# ProProject_HV_Display_2024-06-08.net
KiCad netlist of a schematic drawn in EasyEDA Pro
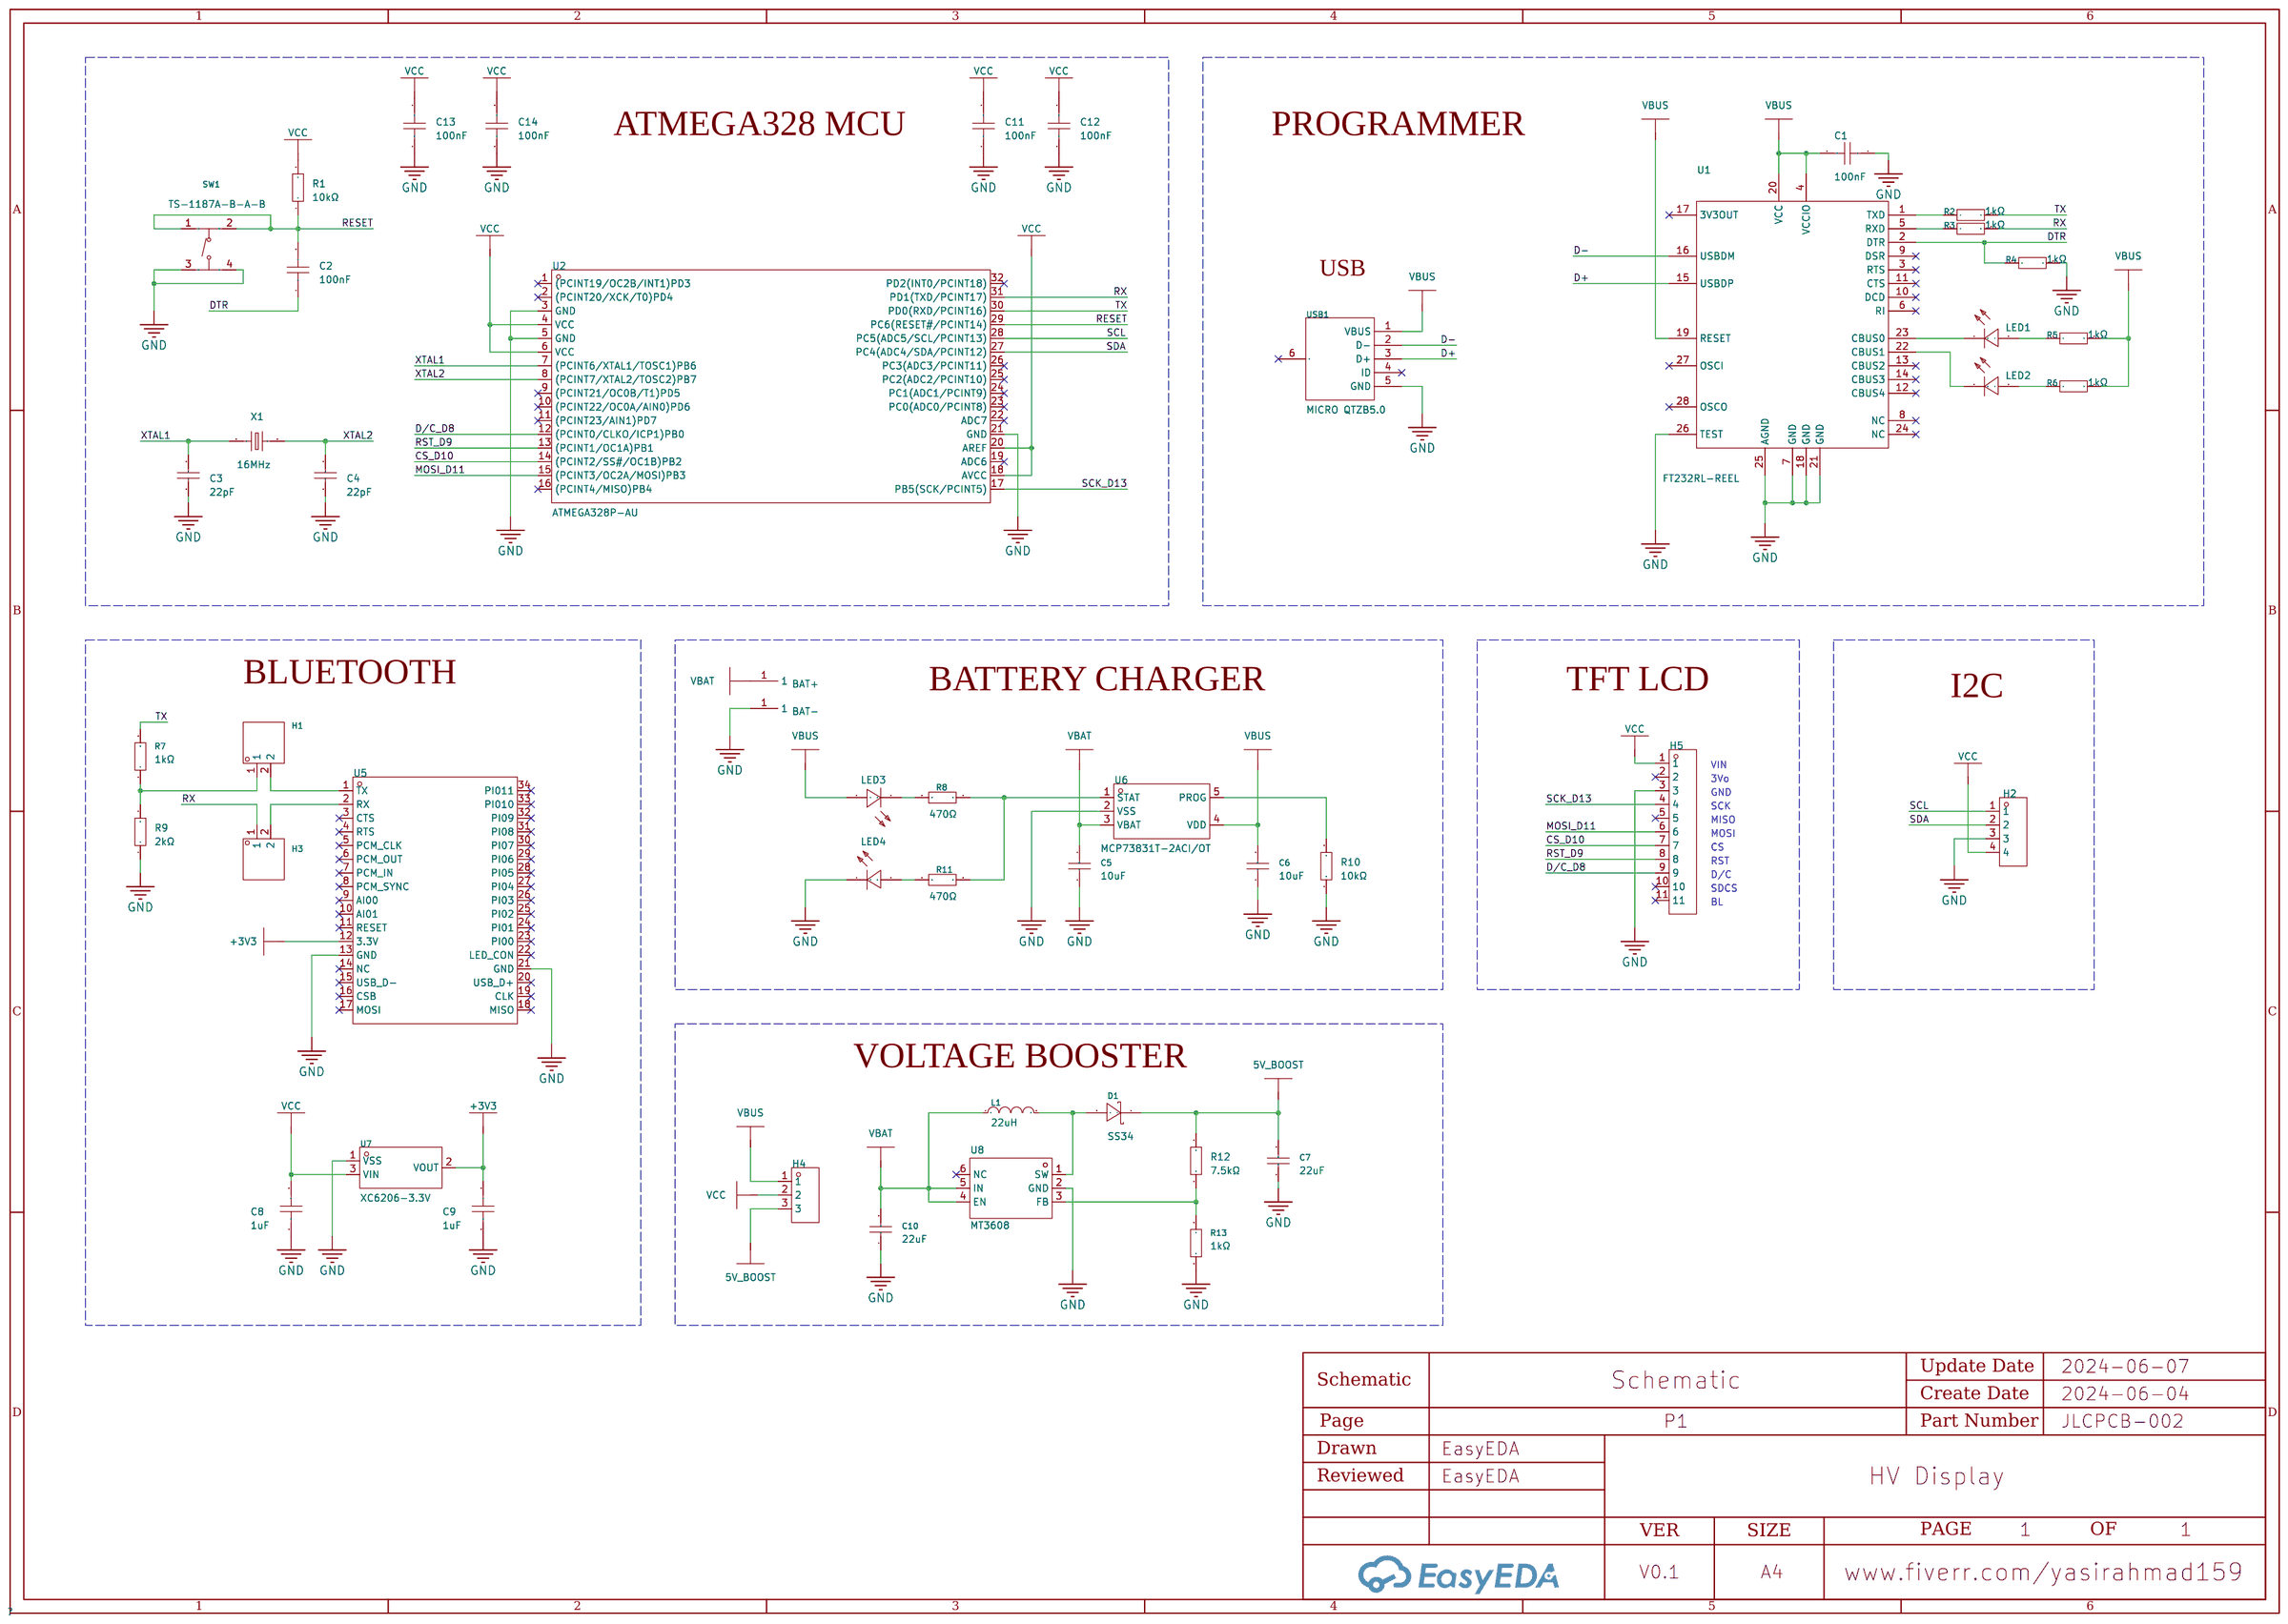
[diagram p0: schematic sheet]

(export (version "E")
  (design (tool "Eeschema 10.0.6"))
  (components
    (comp (ref "C1")
      (value "100nF")
      (footprint "easyedapro:C0402")
      (fields
        (field (name "Manufacturer Part") "CL05B104KB54PNC")
        (field (name "Manufacturer") "SAMSUNG(三星)")
      )
      (libsource (lib "easyedapro") (part "CL05B104KB54PNC"))
    )
    (comp (ref "C2")
      (value "100nF")
      (footprint "easyedapro:C0402")
      (fields
        (field (name "Manufacturer Part") "CL05B104KB54PNC")
        (field (name "Manufacturer") "SAMSUNG(三星)")
      )
      (libsource (lib "easyedapro") (part "CL05B104KB54PNC"))
    )
    (comp (ref "C3")
      (value "22pF")
      (footprint "easyedapro:C0402")
      (fields (field (name "Manufacturer Part") "0402CG220J500NT") (field (name "Manufacturer") "FH(风华)"))
      (libsource (lib "easyedapro") (part "0402CG220J500NT"))
    )
    (comp (ref "C4")
      (value "22pF")
      (footprint "easyedapro:C0402")
      (fields (field (name "Manufacturer Part") "0402CG220J500NT") (field (name "Manufacturer") "FH(风华)"))
      (libsource (lib "easyedapro") (part "0402CG220J500NT"))
    )
    (comp (ref "C5")
      (value "10uF")
      (footprint "easyedapro:C0402")
      (fields
        (field (name "Manufacturer Part") "CL05A106MQ5NUNC")
        (field (name "Manufacturer") "SAMSUNG(三星)")
      )
      (libsource (lib "easyedapro") (part "CL05A106MQ5NUNC"))
    )
    (comp (ref "C6")
      (value "10uF")
      (footprint "easyedapro:C0402")
      (fields
        (field (name "Manufacturer Part") "CL05A106MQ5NUNC")
        (field (name "Manufacturer") "SAMSUNG(三星)")
      )
      (libsource (lib "easyedapro") (part "CL05A106MQ5NUNC"))
    )
    (comp (ref "C7")
      (value "22uF")
      (footprint "easyedapro:C1812")
      (fields (field (name "Manufacturer Part") "1812X226K250NT") (field (name "Manufacturer") "FH(风华)"))
      (libsource (lib "easyedapro") (part "1812X226K250NT"))
    )
    (comp (ref "C8")
      (value "1uF")
      (footprint "easyedapro:C0402")
      (fields
        (field (name "Manufacturer Part") "CL05A105KA5NQNC")
        (field (name "Manufacturer") "SAMSUNG(三星)")
      )
      (libsource (lib "easyedapro") (part "CL05A105KA5NQNC"))
    )
    (comp (ref "C9")
      (value "1uF")
      (footprint "easyedapro:C0402")
      (fields
        (field (name "Manufacturer Part") "CL05A105KA5NQNC")
        (field (name "Manufacturer") "SAMSUNG(三星)")
      )
      (libsource (lib "easyedapro") (part "CL05A105KA5NQNC"))
    )
    (comp (ref "C10")
      (value "22uF")
      (footprint "easyedapro:C1812")
      (fields (field (name "Manufacturer Part") "1812X226K250NT") (field (name "Manufacturer") "FH(风华)"))
      (libsource (lib "easyedapro") (part "1812X226K250NT"))
    )
    (comp (ref "C11")
      (value "100nF")
      (footprint "easyedapro:C0402")
      (fields
        (field (name "Manufacturer Part") "CL05B104KB54PNC")
        (field (name "Manufacturer") "SAMSUNG(三星)")
      )
      (libsource (lib "easyedapro") (part "CL05B104KB54PNC"))
    )
    (comp (ref "C12")
      (value "100nF")
      (footprint "easyedapro:C0402")
      (fields
        (field (name "Manufacturer Part") "CL05B104KB54PNC")
        (field (name "Manufacturer") "SAMSUNG(三星)")
      )
      (libsource (lib "easyedapro") (part "CL05B104KB54PNC"))
    )
    (comp (ref "C13")
      (value "100nF")
      (footprint "easyedapro:C0402")
      (fields
        (field (name "Manufacturer Part") "CL05B104KB54PNC")
        (field (name "Manufacturer") "SAMSUNG(三星)")
      )
      (libsource (lib "easyedapro") (part "CL05B104KB54PNC"))
    )
    (comp (ref "C14")
      (value "100nF")
      (footprint "easyedapro:C0402")
      (fields
        (field (name "Manufacturer Part") "CL05B104KB54PNC")
        (field (name "Manufacturer") "SAMSUNG(三星)")
      )
      (libsource (lib "easyedapro") (part "CL05B104KB54PNC"))
    )
    (comp (ref "D1")
      (value "SS34")
      (footprint "easyedapro:SMA_L4.3-W2.6-LS5.2-RD")
      (fields (field (name "Manufacturer") "MDD"))
      (libsource (lib "easyedapro") (part "SS34_C8678"))
    )
    (comp (ref "H1")
      (value "~")
      (footprint "easyedapro:HDR-TH_2P-P2.54-V-M-1")
      (libsource (lib "easyedapro") (part "210S-1*2P L=11.6MMGold-plated black"))
    )
    (comp (ref "H2")
      (value "~")
      (footprint "easyedapro:HDR-TH_4P-P2.54-V-M")
      (libsource (lib "easyedapro") (part "PZ254V-11-04P"))
    )
    (comp (ref "H3")
      (value "~")
      (footprint "easyedapro:HDR-TH_2P-P2.54-V-M-1")
      (libsource (lib "easyedapro") (part "210S-1*2P L=11.6MMGold-plated black"))
    )
    (comp (ref "H4")
      (value "~")
      (footprint "easyedapro:HDR-TH_3P-P2.54-V-M")
      (libsource (lib "easyedapro") (part "PZ254V-11-03P_C2937625"))
    )
    (comp (ref "H5")
      (value "~")
      (footprint "easyedapro:HDR-TH_11P-P2.54-V-M")
      (libsource (lib "easyedapro") (part "PZ254-1-11-Z-8.5"))
    )
    (comp (ref "L1")
      (value "22uH")
      (footprint "easyedapro:IND-SMD_L7.0-W6.8")
      (fields (field (name "Manufacturer Part") "SMRH74-220MT") (field (name "Manufacturer") "SXN(顺翔诺)"))
      (libsource (lib "easyedapro") (part "SMRH74-220MT"))
    )
    (comp (ref "LED1")
      (value "TJ-S1005SW4TGLC2R-A5")
      (footprint "easyedapro:LED0402-RD")
      (description "Emitted Color:Red")
      (fields (field (name "Manufacturer") "TOGIALED(统佳)"))
      (libsource (lib "easyedapro") (part "TJ-S1005SW4TGLC2R-A5"))
    )
    (comp (ref "LED2")
      (value "TJ-S1005SW4TGLC2R-A5")
      (footprint "easyedapro:LED0402-RD")
      (description "Emitted Color:Red")
      (fields (field (name "Manufacturer") "TOGIALED(统佳)"))
      (libsource (lib "easyedapro") (part "TJ-S1005SW4TGLC2R-A5"))
    )
    (comp (ref "LED3")
      (value "TJ-S1005SW4TGLC2R-A5")
      (footprint "easyedapro:LED0402-RD")
      (description "Emitted Color:Red")
      (fields (field (name "Manufacturer") "TOGIALED(统佳)"))
      (libsource (lib "easyedapro") (part "TJ-S1005SW4TGLC2R-A5"))
    )
    (comp (ref "LED4")
      (value "TJ-S1005SW4TGLC7K-A5")
      (footprint "easyedapro:LED0402-RD_GREEN")
      (description "Emitted Color:Green-yellow")
      (fields (field (name "Manufacturer") "TOGIALED(统佳)"))
      (libsource (lib "easyedapro") (part "TJ-S1005SW4TGLC7K-A5"))
    )
    (comp (ref "R1")
      (value "10kΩ")
      (footprint "easyedapro:R0402")
      (fields
        (field (name "Manufacturer Part") "0402WGF1002TCE")
        (field (name "Manufacturer") "UNI-ROYAL(厚声)")
      )
      (libsource (lib "easyedapro") (part "0402WGF1002TCE"))
    )
    (comp (ref "R2")
      (value "1kΩ")
      (footprint "easyedapro:R0402")
      (fields
        (field (name "Manufacturer Part") "0402WGF1001TCE")
        (field (name "Manufacturer") "UNI-ROYAL(厚声)")
      )
      (libsource (lib "easyedapro") (part "0402WGF1001TCE"))
    )
    (comp (ref "R3")
      (value "1kΩ")
      (footprint "easyedapro:R0402")
      (fields
        (field (name "Manufacturer Part") "0402WGF1001TCE")
        (field (name "Manufacturer") "UNI-ROYAL(厚声)")
      )
      (libsource (lib "easyedapro") (part "0402WGF1001TCE"))
    )
    (comp (ref "R4")
      (value "1kΩ")
      (footprint "easyedapro:R0402")
      (fields
        (field (name "Manufacturer Part") "0402WGF1001TCE")
        (field (name "Manufacturer") "UNI-ROYAL(厚声)")
      )
      (libsource (lib "easyedapro") (part "0402WGF1001TCE"))
    )
    (comp (ref "R5")
      (value "1kΩ")
      (footprint "easyedapro:R0402")
      (fields
        (field (name "Manufacturer Part") "0402WGF1001TCE")
        (field (name "Manufacturer") "UNI-ROYAL(厚声)")
      )
      (libsource (lib "easyedapro") (part "0402WGF1001TCE"))
    )
    (comp (ref "R6")
      (value "1kΩ")
      (footprint "easyedapro:R0402")
      (fields
        (field (name "Manufacturer Part") "0402WGF1001TCE")
        (field (name "Manufacturer") "UNI-ROYAL(厚声)")
      )
      (libsource (lib "easyedapro") (part "0402WGF1001TCE"))
    )
    (comp (ref "R7")
      (value "1kΩ")
      (footprint "easyedapro:R0402")
      (fields
        (field (name "Manufacturer Part") "0402WGF1001TCE")
        (field (name "Manufacturer") "UNI-ROYAL(厚声)")
      )
      (libsource (lib "easyedapro") (part "0402WGF1001TCE"))
    )
    (comp (ref "R8")
      (value "470Ω")
      (footprint "easyedapro:R0402")
      (fields
        (field (name "Manufacturer Part") "0402WGF4700TCE")
        (field (name "Manufacturer") "UNI-ROYAL(厚声)")
      )
      (libsource (lib "easyedapro") (part "0402WGF4700TCE"))
    )
    (comp (ref "R9")
      (value "2kΩ")
      (footprint "easyedapro:R0402")
      (fields
        (field (name "Manufacturer Part") "0402WGF2001TCE")
        (field (name "Manufacturer") "UNI-ROYAL(厚声)")
      )
      (libsource (lib "easyedapro") (part "0402WGF2001TCE"))
    )
    (comp (ref "R10")
      (value "10kΩ")
      (footprint "easyedapro:R0402")
      (fields
        (field (name "Manufacturer Part") "0402WGF1002TCE")
        (field (name "Manufacturer") "UNI-ROYAL(厚声)")
      )
      (libsource (lib "easyedapro") (part "0402WGF1002TCE"))
    )
    (comp (ref "R11")
      (value "470Ω")
      (footprint "easyedapro:R0402")
      (fields
        (field (name "Manufacturer Part") "0402WGF4700TCE")
        (field (name "Manufacturer") "UNI-ROYAL(厚声)")
      )
      (libsource (lib "easyedapro") (part "0402WGF4700TCE"))
    )
    (comp (ref "R12")
      (value "7.5kΩ")
      (footprint "easyedapro:R0402")
      (fields (field (name "Manufacturer Part") "WR04X7501FTL") (field (name "Manufacturer") "Walsin(华新科)"))
      (libsource (lib "easyedapro") (part "WR04X7501FTL"))
    )
    (comp (ref "R13")
      (value "1kΩ")
      (footprint "easyedapro:R0402")
      (fields
        (field (name "Manufacturer Part") "0402WGF1001TCE")
        (field (name "Manufacturer") "UNI-ROYAL(厚声)")
      )
      (libsource (lib "easyedapro") (part "0402WGF1001TCE"))
    )
    (comp (ref "SW1")
      (value "TS-1187A-B-A-B")
      (footprint "easyedapro:SW-SMD_4P-L5.1-W5.1-P3.70-LS6.5-TL-2")
      (fields (field (name "Manufacturer") "XKB Connectivity(中国星坤)"))
      (libsource (lib "easyedapro") (part "TS-1187A-B-A-B"))
    )
    (comp (ref "U1")
      (value "FT232RL-REEL")
      (footprint "easyedapro:SSOP-28_L10.2-W5.3-P0.65-LS7.8-BL")
      (fields (field (name "Manufacturer") "FTDI(飞特帝亚)"))
      (libsource (lib "easyedapro") (part "FT232RL-REEL"))
    )
    (comp (ref "U2")
      (value "ATMEGA328P-AU")
      (footprint "easyedapro:TQFP-32_L7.0-W7.0-P0.80-LS9.0-BL")
      (fields (field (name "Manufacturer") "MICROCHIP(美国微芯)"))
      (libsource (lib "easyedapro") (part "ATMEGA328P-AU"))
    )
    (comp (ref "U3")
      (value "BAT+")
      (footprint "easyedapro:TESTPOINT-TH_BD3.2")
      (fields (field (name "Manufacturer Part") "TP-黑色测试点"))
      (libsource (lib "easyedapro") (part "TP-黑色测试点"))
    )
    (comp (ref "U4")
      (value "BAT-")
      (footprint "easyedapro:TESTPOINT-TH_BD3.2")
      (fields (field (name "Manufacturer Part") "TP-黑色测试点"))
      (libsource (lib "easyedapro") (part "TP-黑色测试点"))
    )
    (comp (ref "U5")
      (value "{ManufacturerPart!}")
      (footprint "easyedapro:BULETM-SMD_HC-05")
      (fields (field (name "Manufacturer Part") "HC-05"))
      (libsource (lib "easyedapro") (part "HC-05"))
    )
    (comp (ref "U6")
      (value "MCP73831T-2ACI/OT")
      (footprint "easyedapro:SOT-23-5_L3.0-W1.7-P0.95-LS2.8-BL")
      (fields (field (name "Manufacturer") "MICROCHIP(美国微芯)"))
      (libsource (lib "easyedapro") (part "MCP73831T-2ACI/OT"))
    )
    (comp (ref "U7")
      (value "XC6206-3.3V")
      (footprint "easyedapro:SSOT-3_L2.9-W1.6-P0.95-LS2.8-BR")
      (fields (field (name "Manufacturer") "YONGYUTAI(永裕泰)"))
      (libsource (lib "easyedapro") (part "XC6206-3.3V"))
    )
    (comp (ref "U8")
      (value "MT3608")
      (footprint "easyedapro:SOT-23-6_L2.9-W1.6-P0.95-LS2.8-BL")
      (fields (field (name "Manufacturer") "西安航天民芯"))
      (libsource (lib "easyedapro") (part "MT3608"))
    )
    (comp (ref "USB1")
      (value "MICRO QTZB5.0")
      (footprint "easyedapro:MICRO-USB-SMD_MICRO-QTZB5.0")
      (fields (field (name "Manufacturer") "SHOU HAN(首韩)"))
      (libsource (lib "easyedapro") (part "MICRO QTZB5.0"))
    )
    (comp (ref "X1")
      (value "16MHz")
      (footprint "easyedapro:HC-49S_L11.4-W4.8")
      (fields (field (name "Manufacturer Part") "TAXM16M2GLFBET2T") (field (name "Manufacturer") "YJX(雅晶鑫)"))
      (libsource (lib "easyedapro") (part "HC-49SM16MHz20pF30ppm"))
    )
  )
  (nets
    (net (code "1") (name "+3V3") (class "Default")
      (node (ref "C9") (pin "2") (pinfunction "2_2") (pintype "unspecified"))
      (node (ref "U5") (pin "12") (pinfunction "3.3V_12") (pintype "input"))
      (node (ref "U7") (pin "2") (pinfunction "VOUT_2") (pintype "input"))
    )
    (net (code "2") (name "/CS_D10") (class "Default")
      (node (ref "H5") (pin "7") (pinfunction "7_7") (pintype "unspecified"))
      (node (ref "U2") (pin "14") (pinfunction "(PCINT2/SS#/OC1B)PB2_14") (pintype "unspecified"))
    )
    (net (code "3") (name "/D+") (class "Default")
      (node (ref "U1") (pin "15") (pinfunction "USBDP_15") (pintype "bidirectional"))
      (node (ref "USB1") (pin "3") (pinfunction "D+_3") (pintype "input"))
    )
    (net (code "4") (name "/D-") (class "Default")
      (node (ref "U1") (pin "16") (pinfunction "USBDM_16") (pintype "bidirectional"))
      (node (ref "USB1") (pin "2") (pinfunction "D-_2") (pintype "input"))
    )
    (net (code "5") (name "/DTR") (class "Default")
      (node (ref "C2") (pin "1") (pinfunction "1_1") (pintype "input"))
      (node (ref "R4") (pin "1") (pinfunction "1_1") (pintype "input"))
      (node (ref "U1") (pin "2") (pinfunction "DTR_2") (pintype "output"))
    )
    (net (code "6") (name "/D{slash}C_D8") (class "Default")
      (node (ref "H5") (pin "9") (pinfunction "9_9") (pintype "unspecified"))
      (node (ref "U2") (pin "12") (pinfunction "(PCINT0/CLKO/ICP1)PB0_12") (pintype "unspecified"))
    )
    (net (code "7") (name "/MOSI_D11") (class "Default")
      (node (ref "H5") (pin "6") (pinfunction "6_6") (pintype "unspecified"))
      (node (ref "U2") (pin "15") (pinfunction "(PCINT3/OC2A/MOSI)PB3_15") (pintype "unspecified"))
    )
    (net (code "8") (name "/RESET") (class "Default")
      (node (ref "C2") (pin "2") (pinfunction "2_2") (pintype "input"))
      (node (ref "R1") (pin "1") (pinfunction "1_1") (pintype "input"))
      (node (ref "SW1") (pin "1") (pinfunction "A_1") (pintype "input"))
      (node (ref "SW1") (pin "2") (pinfunction "B_2") (pintype "input"))
      (node (ref "U2") (pin "29") (pinfunction "PC6(RESET#/PCINT14)_29") (pintype "unspecified"))
    )
    (net (code "9") (name "/RST_D9") (class "Default")
      (node (ref "H5") (pin "8") (pinfunction "8_8") (pintype "unspecified"))
      (node (ref "U2") (pin "13") (pinfunction "(PCINT1/OC1A)PB1_13") (pintype "unspecified"))
    )
    (net (code "10") (name "/RX") (class "Default")
      (node (ref "H3") (pin "1") (pinfunction "1_1") (pintype "input"))
      (node (ref "R3") (pin "2") (pinfunction "2_2") (pintype "input"))
      (node (ref "U2") (pin "31") (pinfunction "PD1(TXD/PCINT17)_31") (pintype "unspecified"))
    )
    (net (code "11") (name "/SCK_D13") (class "Default")
      (node (ref "H5") (pin "4") (pinfunction "4_4") (pintype "unspecified"))
      (node (ref "U2") (pin "17") (pinfunction "PB5(SCK/PCINT5)_17") (pintype "unspecified"))
    )
    (net (code "12") (name "/SCL") (class "Default")
      (node (ref "H2") (pin "1") (pinfunction "1_1") (pintype "unspecified"))
      (node (ref "U2") (pin "28") (pinfunction "PC5(ADC5/SCL/PCINT13)_28") (pintype "unspecified"))
    )
    (net (code "13") (name "/SDA") (class "Default")
      (node (ref "H2") (pin "2") (pinfunction "2_2") (pintype "unspecified"))
      (node (ref "U2") (pin "27") (pinfunction "PC4(ADC4/SDA/PCINT12)_27") (pintype "unspecified"))
    )
    (net (code "14") (name "/TX") (class "Default")
      (node (ref "R2") (pin "2") (pinfunction "2_2") (pintype "input"))
      (node (ref "R7") (pin "2") (pinfunction "2_2") (pintype "input"))
      (node (ref "U2") (pin "30") (pinfunction "PD0(RXD/PCINT16)_30") (pintype "unspecified"))
    )
    (net (code "15") (name "/XTAL1") (class "Default")
      (node (ref "C3") (pin "2") (pinfunction "2_2") (pintype "input"))
      (node (ref "U2") (pin "7") (pinfunction "(PCINT6/XTAL1/TOSC1)PB6_7") (pintype "unspecified"))
      (node (ref "X1") (pin "1") (pinfunction "1_1") (pintype "unspecified"))
    )
    (net (code "16") (name "/XTAL2") (class "Default")
      (node (ref "C4") (pin "2") (pinfunction "2_2") (pintype "input"))
      (node (ref "U2") (pin "8") (pinfunction "(PCINT7/XTAL2/TOSC2)PB7_8") (pintype "unspecified"))
      (node (ref "X1") (pin "2") (pinfunction "2_2") (pintype "unspecified"))
    )
    (net (code "17") (name "5V_BOOST") (class "Default")
      (node (ref "C7") (pin "2") (pinfunction "2_2") (pintype "input"))
      (node (ref "D1") (pin "1") (pinfunction "K_1") (pintype "input"))
      (node (ref "H4") (pin "3") (pinfunction "3_3") (pintype "input"))
      (node (ref "R12") (pin "2") (pinfunction "2_2") (pintype "unspecified"))
    )
    (net (code "18") (name "GND") (class "Default")
      (node (ref "C1") (pin "1") (pinfunction "1_1") (pintype "input"))
      (node (ref "C10") (pin "1") (pinfunction "1_1") (pintype "input"))
      (node (ref "C11") (pin "1") (pinfunction "1_1") (pintype "input"))
      (node (ref "C12") (pin "1") (pinfunction "1_1") (pintype "input"))
      (node (ref "C13") (pin "1") (pinfunction "1_1") (pintype "input"))
      (node (ref "C14") (pin "1") (pinfunction "1_1") (pintype "input"))
      (node (ref "C3") (pin "1") (pinfunction "1_1") (pintype "input"))
      (node (ref "C4") (pin "1") (pinfunction "1_1") (pintype "input"))
      (node (ref "C5") (pin "1") (pinfunction "1_1") (pintype "input"))
      (node (ref "C6") (pin "1") (pinfunction "1_1") (pintype "input"))
      (node (ref "C7") (pin "1") (pinfunction "1_1") (pintype "input"))
      (node (ref "C8") (pin "1") (pinfunction "1_1") (pintype "unspecified"))
      (node (ref "C9") (pin "1") (pinfunction "1_1") (pintype "unspecified"))
      (node (ref "H2") (pin "3") (pinfunction "3_3") (pintype "unspecified"))
      (node (ref "H5") (pin "3") (pinfunction "3_3") (pintype "unspecified"))
      (node (ref "LED4") (pin "1") (pinfunction "C_1") (pintype "unspecified"))
      (node (ref "R10") (pin "1") (pinfunction "1_1") (pintype "input"))
      (node (ref "R13") (pin "1") (pinfunction "1_1") (pintype "input"))
      (node (ref "R4") (pin "2") (pinfunction "2_2") (pintype "input"))
      (node (ref "R9") (pin "1") (pinfunction "1_1") (pintype "input"))
      (node (ref "SW1") (pin "3") (pinfunction "C_3") (pintype "input"))
      (node (ref "SW1") (pin "4") (pinfunction "D_4") (pintype "input"))
      (node (ref "U1") (pin "18") (pinfunction "GND_18") (pintype "unspecified"))
      (node (ref "U1") (pin "21") (pinfunction "GND_21") (pintype "unspecified"))
      (node (ref "U1") (pin "25") (pinfunction "AGND_25") (pintype "unspecified"))
      (node (ref "U1") (pin "26") (pinfunction "TEST_26") (pintype "unspecified"))
      (node (ref "U1") (pin "7") (pinfunction "GND_7") (pintype "unspecified"))
      (node (ref "U2") (pin "21") (pinfunction "GND_21") (pintype "unspecified"))
      (node (ref "U2") (pin "3") (pinfunction "GND_3") (pintype "unspecified"))
      (node (ref "U2") (pin "5") (pinfunction "GND_5") (pintype "unspecified"))
      (node (ref "U4") (pin "1") (pinfunction "1_1") (pintype "input"))
      (node (ref "U5") (pin "13") (pinfunction "GND_13") (pintype "input"))
      (node (ref "U5") (pin "21") (pinfunction "GND_21") (pintype "input"))
      (node (ref "U6") (pin "2") (pinfunction "VSS_2") (pintype "input"))
      (node (ref "U7") (pin "1") (pinfunction "VSS_1") (pintype "input"))
      (node (ref "U8") (pin "2") (pinfunction "GND_2") (pintype "input"))
      (node (ref "USB1") (pin "5") (pinfunction "GND_5") (pintype "input"))
    )
    (net (code "19") (name "Net-(D1-A)") (class "Default")
      (node (ref "D1") (pin "2") (pinfunction "A_2") (pintype "input"))
      (node (ref "L1") (pin "2") (pinfunction "2_2") (pintype "input"))
      (node (ref "U8") (pin "1") (pinfunction "SW_1") (pintype "input"))
    )
    (net (code "20") (name "Net-(H1-Pad1)") (class "Default")
      (node (ref "H1") (pin "1") (pinfunction "1_1") (pintype "input"))
      (node (ref "R7") (pin "1") (pinfunction "1_1") (pintype "input"))
      (node (ref "R9") (pin "2") (pinfunction "2_2") (pintype "input"))
    )
    (net (code "21") (name "Net-(LED1-A)") (class "Default")
      (node (ref "LED1") (pin "2") (pinfunction "A_2") (pintype "unspecified"))
      (node (ref "R5") (pin "1") (pinfunction "1_1") (pintype "input"))
    )
    (net (code "22") (name "Net-(LED1-C)") (class "Default")
      (node (ref "LED1") (pin "1") (pinfunction "C_1") (pintype "unspecified"))
      (node (ref "U1") (pin "23") (pinfunction "CBUS0_23") (pintype "bidirectional"))
    )
    (net (code "23") (name "Net-(LED2-A)") (class "Default")
      (node (ref "LED2") (pin "2") (pinfunction "A_2") (pintype "unspecified"))
      (node (ref "R6") (pin "1") (pinfunction "1_1") (pintype "input"))
    )
    (net (code "24") (name "Net-(LED2-C)") (class "Default")
      (node (ref "LED2") (pin "1") (pinfunction "C_1") (pintype "unspecified"))
      (node (ref "U1") (pin "22") (pinfunction "CBUS1_22") (pintype "bidirectional"))
    )
    (net (code "25") (name "Net-(LED3-C)") (class "Default")
      (node (ref "LED3") (pin "1") (pinfunction "C_1") (pintype "unspecified"))
      (node (ref "R8") (pin "1") (pinfunction "1_1") (pintype "input"))
    )
    (net (code "26") (name "Net-(LED4-A)") (class "Default")
      (node (ref "LED4") (pin "2") (pinfunction "A_2") (pintype "unspecified"))
      (node (ref "R11") (pin "1") (pinfunction "1_1") (pintype "input"))
    )
    (net (code "27") (name "Net-(U1-RXD)") (class "Default")
      (node (ref "R3") (pin "1") (pinfunction "1_1") (pintype "input"))
      (node (ref "U1") (pin "5") (pinfunction "RXD_5") (pintype "unspecified"))
    )
    (net (code "28") (name "Net-(U1-TXD)") (class "Default")
      (node (ref "R2") (pin "1") (pinfunction "1_1") (pintype "input"))
      (node (ref "U1") (pin "1") (pinfunction "TXD_1") (pintype "output"))
    )
    (net (code "29") (name "Net-(U5-RX)") (class "Default")
      (node (ref "H3") (pin "2") (pinfunction "2_2") (pintype "input"))
      (node (ref "U5") (pin "2") (pinfunction "RX_2") (pintype "input"))
    )
    (net (code "30") (name "Net-(U5-TX)") (class "Default")
      (node (ref "H1") (pin "2") (pinfunction "2_2") (pintype "input"))
      (node (ref "U5") (pin "1") (pinfunction "TX_1") (pintype "input"))
    )
    (net (code "31") (name "Net-(U6-PROG)") (class "Default")
      (node (ref "R10") (pin "2") (pinfunction "2_2") (pintype "input"))
      (node (ref "U6") (pin "5") (pinfunction "PROG_5") (pintype "input"))
    )
    (net (code "32") (name "Net-(U6-STAT)") (class "Default")
      (node (ref "R11") (pin "2") (pinfunction "2_2") (pintype "input"))
      (node (ref "R8") (pin "2") (pinfunction "2_2") (pintype "input"))
      (node (ref "U6") (pin "1") (pinfunction "STAT_1") (pintype "input"))
    )
    (net (code "33") (name "Net-(U8-FB)") (class "Default")
      (node (ref "R12") (pin "1") (pinfunction "1_1") (pintype "unspecified"))
      (node (ref "R13") (pin "2") (pinfunction "2_2") (pintype "input"))
      (node (ref "U8") (pin "3") (pinfunction "FB_3") (pintype "input"))
    )
    (net (code "34") (name "VBAT") (class "Default")
      (node (ref "C10") (pin "2") (pinfunction "2_2") (pintype "input"))
      (node (ref "C5") (pin "2") (pinfunction "2_2") (pintype "input"))
      (node (ref "L1") (pin "1") (pinfunction "1_1") (pintype "input"))
      (node (ref "U3") (pin "1") (pinfunction "1_1") (pintype "input"))
      (node (ref "U6") (pin "3") (pinfunction "VBAT_3") (pintype "input"))
      (node (ref "U8") (pin "4") (pinfunction "EN_4") (pintype "input"))
      (node (ref "U8") (pin "5") (pinfunction "IN_5") (pintype "input"))
    )
    (net (code "35") (name "VBUS") (class "Default")
      (node (ref "C1") (pin "2") (pinfunction "2_2") (pintype "input"))
      (node (ref "C6") (pin "2") (pinfunction "2_2") (pintype "input"))
      (node (ref "H4") (pin "1") (pinfunction "1_1") (pintype "input"))
      (node (ref "LED3") (pin "2") (pinfunction "A_2") (pintype "unspecified"))
      (node (ref "R5") (pin "2") (pinfunction "2_2") (pintype "input"))
      (node (ref "R6") (pin "2") (pinfunction "2_2") (pintype "input"))
      (node (ref "U1") (pin "19") (pinfunction "RESET_19") (pintype "unspecified"))
      (node (ref "U1") (pin "20") (pinfunction "VCC_20") (pintype "unspecified"))
      (node (ref "U1") (pin "4") (pinfunction "VCCIO_4") (pintype "unspecified"))
      (node (ref "U6") (pin "4") (pinfunction "VDD_4") (pintype "input"))
      (node (ref "USB1") (pin "1") (pinfunction "VBUS_1") (pintype "input"))
    )
    (net (code "36") (name "VCC") (class "Default")
      (node (ref "C11") (pin "2") (pinfunction "2_2") (pintype "input"))
      (node (ref "C12") (pin "2") (pinfunction "2_2") (pintype "input"))
      (node (ref "C13") (pin "2") (pinfunction "2_2") (pintype "input"))
      (node (ref "C14") (pin "2") (pinfunction "2_2") (pintype "input"))
      (node (ref "C8") (pin "2") (pinfunction "2_2") (pintype "unspecified"))
      (node (ref "H2") (pin "4") (pinfunction "4_4") (pintype "unspecified"))
      (node (ref "H4") (pin "2") (pinfunction "2_2") (pintype "input"))
      (node (ref "H5") (pin "1") (pinfunction "1_1") (pintype "unspecified"))
      (node (ref "R1") (pin "2") (pinfunction "2_2") (pintype "input"))
      (node (ref "U2") (pin "18") (pinfunction "AVCC_18") (pintype "unspecified"))
      (node (ref "U2") (pin "20") (pinfunction "AREF_20") (pintype "unspecified"))
      (node (ref "U2") (pin "4") (pinfunction "VCC_4") (pintype "unspecified"))
      (node (ref "U2") (pin "6") (pinfunction "VCC_6") (pintype "unspecified"))
      (node (ref "U7") (pin "3") (pinfunction "VIN_3") (pintype "input"))
    )
    (net (code "37") (name "unconnected-(H5-Pad2)") (class "Default")
      (node (ref "H5") (pin "2") (pinfunction "2_2") (pintype "unspecified+no_connect"))
    )
    (net (code "38") (name "unconnected-(H5-Pad5)") (class "Default")
      (node (ref "H5") (pin "5") (pinfunction "5_5") (pintype "unspecified+no_connect"))
    )
    (net (code "39") (name "unconnected-(H5-Pad10)") (class "Default")
      (node (ref "H5") (pin "10") (pinfunction "10_10") (pintype "unspecified+no_connect"))
    )
    (net (code "40") (name "unconnected-(H5-Pad11)") (class "Default")
      (node (ref "H5") (pin "11") (pinfunction "11_11") (pintype "unspecified+no_connect"))
    )
    (net (code "41") (name "unconnected-(U1-3V3OUT-Pad17)") (class "Default")
      (node (ref "U1") (pin "17") (pinfunction "3V3OUT_17") (pintype "output+no_connect"))
    )
    (net (code "42") (name "unconnected-(U1-CBUS2-Pad13)") (class "Default")
      (node (ref "U1") (pin "13") (pinfunction "CBUS2_13") (pintype "bidirectional+no_connect"))
    )
    (net (code "43") (name "unconnected-(U1-CBUS3-Pad14)") (class "Default")
      (node (ref "U1") (pin "14") (pinfunction "CBUS3_14") (pintype "bidirectional+no_connect"))
    )
    (net (code "44") (name "unconnected-(U1-CBUS4-Pad12)") (class "Default")
      (node (ref "U1") (pin "12") (pinfunction "CBUS4_12") (pintype "bidirectional+no_connect"))
    )
    (net (code "45") (name "unconnected-(U1-CTS-Pad11)") (class "Default")
      (node (ref "U1") (pin "11") (pinfunction "CTS_11") (pintype "unspecified+no_connect"))
    )
    (net (code "46") (name "unconnected-(U1-DCD-Pad10)") (class "Default")
      (node (ref "U1") (pin "10") (pinfunction "DCD_10") (pintype "unspecified+no_connect"))
    )
    (net (code "47") (name "unconnected-(U1-DSR-Pad9)") (class "Default")
      (node (ref "U1") (pin "9") (pinfunction "DSR_9") (pintype "unspecified+no_connect"))
    )
    (net (code "48") (name "unconnected-(U1-NC-Pad8)") (class "Default")
      (node (ref "U1") (pin "8") (pinfunction "NC_8") (pintype "unspecified+no_connect"))
    )
    (net (code "49") (name "unconnected-(U1-NC-Pad24)") (class "Default")
      (node (ref "U1") (pin "24") (pinfunction "NC_24") (pintype "unspecified+no_connect"))
    )
    (net (code "50") (name "unconnected-(U1-OSCI-Pad27)") (class "Default")
      (node (ref "U1") (pin "27") (pinfunction "OSCI_27") (pintype "unspecified+no_connect"))
    )
    (net (code "51") (name "unconnected-(U1-OSCO-Pad28)") (class "Default")
      (node (ref "U1") (pin "28") (pinfunction "OSCO_28") (pintype "output+no_connect"))
    )
    (net (code "52") (name "unconnected-(U1-RI-Pad6)") (class "Default")
      (node (ref "U1") (pin "6") (pinfunction "RI_6") (pintype "unspecified+no_connect"))
    )
    (net (code "53") (name "unconnected-(U1-RTS-Pad3)") (class "Default")
      (node (ref "U1") (pin "3") (pinfunction "RTS_3") (pintype "output+no_connect"))
    )
    (net (code "54") (name "unconnected-(U2-(PCINT4{slash}MISO)PB4-Pad16)") (class "Default")
      (node (ref "U2") (pin "16") (pinfunction "(PCINT4/MISO)PB4_16") (pintype "unspecified+no_connect"))
    )
    (net (code "55") (name "unconnected-(U2-(PCINT19{slash}OC2B{slash}INT1)PD3-Pad1)") (class "Default")
      (node (ref "U2") (pin "1") (pinfunction "(PCINT19/OC2B/INT1)PD3_1") (pintype "unspecified+no_connect"))
    )
    (net (code "56") (name "unconnected-(U2-(PCINT20{slash}XCK{slash}T0)PD4-Pad2)") (class "Default")
      (node (ref "U2") (pin "2") (pinfunction "(PCINT20/XCK/T0)PD4_2") (pintype "unspecified+no_connect"))
    )
    (net (code "57") (name "unconnected-(U2-(PCINT21{slash}OC0B{slash}T1)PD5-Pad9)") (class "Default")
      (node (ref "U2") (pin "9") (pinfunction "(PCINT21/OC0B/T1)PD5_9") (pintype "unspecified+no_connect"))
    )
    (net (code "58") (name "unconnected-(U2-(PCINT22{slash}OC0A{slash}AIN0)PD6-Pad10)") (class "Default")
      (node (ref "U2") (pin "10") (pinfunction "(PCINT22/OC0A/AIN0)PD6_10") (pintype "unspecified+no_connect"))
    )
    (net (code "59") (name "unconnected-(U2-(PCINT23{slash}AIN1)PD7-Pad11)") (class "Default")
      (node (ref "U2") (pin "11") (pinfunction "(PCINT23/AIN1)PD7_11") (pintype "unspecified+no_connect"))
    )
    (net (code "60") (name "unconnected-(U2-ADC6-Pad19)") (class "Default")
      (node (ref "U2") (pin "19") (pinfunction "ADC6_19") (pintype "unspecified+no_connect"))
    )
    (net (code "61") (name "unconnected-(U2-ADC7-Pad22)") (class "Default")
      (node (ref "U2") (pin "22") (pinfunction "ADC7_22") (pintype "unspecified+no_connect"))
    )
    (net (code "62") (name "unconnected-(U2-PC0(ADC0{slash}PCINT8)-Pad23)") (class "Default")
      (node (ref "U2") (pin "23") (pinfunction "PC0(ADC0/PCINT8)_23") (pintype "unspecified+no_connect"))
    )
    (net (code "63") (name "unconnected-(U2-PC1(ADC1{slash}PCINT9)-Pad24)") (class "Default")
      (node (ref "U2") (pin "24") (pinfunction "PC1(ADC1/PCINT9)_24") (pintype "unspecified+no_connect"))
    )
    (net (code "64") (name "unconnected-(U2-PC2(ADC2{slash}PCINT10)-Pad25)") (class "Default")
      (node (ref "U2") (pin "25") (pinfunction "PC2(ADC2/PCINT10)_25") (pintype "unspecified+no_connect"))
    )
    (net (code "65") (name "unconnected-(U2-PC3(ADC3{slash}PCINT11)-Pad26)") (class "Default")
      (node (ref "U2") (pin "26") (pinfunction "PC3(ADC3/PCINT11)_26") (pintype "unspecified+no_connect"))
    )
    (net (code "66") (name "unconnected-(U2-PD2(INT0{slash}PCINT18)-Pad32)") (class "Default")
      (node (ref "U2") (pin "32") (pinfunction "PD2(INT0/PCINT18)_32") (pintype "unspecified+no_connect"))
    )
    (net (code "67") (name "unconnected-(U5-AI00-Pad9)") (class "Default")
      (node (ref "U5") (pin "9") (pinfunction "AI00_9") (pintype "input+no_connect"))
    )
    (net (code "68") (name "unconnected-(U5-AI01-Pad10)") (class "Default")
      (node (ref "U5") (pin "10") (pinfunction "AI01_10") (pintype "input+no_connect"))
    )
    (net (code "69") (name "unconnected-(U5-CLK-Pad19)") (class "Default")
      (node (ref "U5") (pin "19") (pinfunction "CLK_19") (pintype "input+no_connect"))
    )
    (net (code "70") (name "unconnected-(U5-CSB-Pad16)") (class "Default")
      (node (ref "U5") (pin "16") (pinfunction "CSB_16") (pintype "input+no_connect"))
    )
    (net (code "71") (name "unconnected-(U5-CTS-Pad3)") (class "Default")
      (node (ref "U5") (pin "3") (pinfunction "CTS_3") (pintype "input+no_connect"))
    )
    (net (code "72") (name "unconnected-(U5-LED_CON-Pad22)") (class "Default")
      (node (ref "U5") (pin "22") (pinfunction "LED_CON_22") (pintype "input+no_connect"))
    )
    (net (code "73") (name "unconnected-(U5-MISO-Pad18)") (class "Default")
      (node (ref "U5") (pin "18") (pinfunction "MISO_18") (pintype "input+no_connect"))
    )
    (net (code "74") (name "unconnected-(U5-MOSI-Pad17)") (class "Default")
      (node (ref "U5") (pin "17") (pinfunction "MOSI_17") (pintype "input+no_connect"))
    )
    (net (code "75") (name "unconnected-(U5-NC-Pad14)") (class "Default")
      (node (ref "U5") (pin "14") (pinfunction "NC_14") (pintype "input+no_connect"))
    )
    (net (code "76") (name "unconnected-(U5-PCM_CLK-Pad5)") (class "Default")
      (node (ref "U5") (pin "5") (pinfunction "PCM_CLK_5") (pintype "input+no_connect"))
    )
    (net (code "77") (name "unconnected-(U5-PCM_IN-Pad7)") (class "Default")
      (node (ref "U5") (pin "7") (pinfunction "PCM_IN_7") (pintype "input+no_connect"))
    )
    (net (code "78") (name "unconnected-(U5-PCM_OUT-Pad6)") (class "Default")
      (node (ref "U5") (pin "6") (pinfunction "PCM_OUT_6") (pintype "input+no_connect"))
    )
    (net (code "79") (name "unconnected-(U5-PCM_SYNC-Pad8)") (class "Default")
      (node (ref "U5") (pin "8") (pinfunction "PCM_SYNC_8") (pintype "input+no_connect"))
    )
    (net (code "80") (name "unconnected-(U5-PI00-Pad23)") (class "Default")
      (node (ref "U5") (pin "23") (pinfunction "PI00_23") (pintype "input+no_connect"))
    )
    (net (code "81") (name "unconnected-(U5-PI01-Pad24)") (class "Default")
      (node (ref "U5") (pin "24") (pinfunction "PI01_24") (pintype "input+no_connect"))
    )
    (net (code "82") (name "unconnected-(U5-PI02-Pad25)") (class "Default")
      (node (ref "U5") (pin "25") (pinfunction "PI02_25") (pintype "input+no_connect"))
    )
    (net (code "83") (name "unconnected-(U5-PI03-Pad26)") (class "Default")
      (node (ref "U5") (pin "26") (pinfunction "PI03_26") (pintype "input+no_connect"))
    )
    (net (code "84") (name "unconnected-(U5-PI04-Pad27)") (class "Default")
      (node (ref "U5") (pin "27") (pinfunction "PI04_27") (pintype "input+no_connect"))
    )
    (net (code "85") (name "unconnected-(U5-PI05-Pad28)") (class "Default")
      (node (ref "U5") (pin "28") (pinfunction "PI05_28") (pintype "input+no_connect"))
    )
    (net (code "86") (name "unconnected-(U5-PI06-Pad29)") (class "Default")
      (node (ref "U5") (pin "29") (pinfunction "PI06_29") (pintype "input+no_connect"))
    )
    (net (code "87") (name "unconnected-(U5-PI07-Pad30)") (class "Default")
      (node (ref "U5") (pin "30") (pinfunction "PI07_30") (pintype "input+no_connect"))
    )
    (net (code "88") (name "unconnected-(U5-PI08-Pad31)") (class "Default")
      (node (ref "U5") (pin "31") (pinfunction "PI08_31") (pintype "input+no_connect"))
    )
    (net (code "89") (name "unconnected-(U5-PI09-Pad32)") (class "Default")
      (node (ref "U5") (pin "32") (pinfunction "PI09_32") (pintype "input+no_connect"))
    )
    (net (code "90") (name "unconnected-(U5-PI010-Pad33)") (class "Default")
      (node (ref "U5") (pin "33") (pinfunction "PI010_33") (pintype "input+no_connect"))
    )
    (net (code "91") (name "unconnected-(U5-PI011-Pad34)") (class "Default")
      (node (ref "U5") (pin "34") (pinfunction "PI011_34") (pintype "input+no_connect"))
    )
    (net (code "92") (name "unconnected-(U5-RESET-Pad11)") (class "Default")
      (node (ref "U5") (pin "11") (pinfunction "RESET_11") (pintype "input+no_connect"))
    )
    (net (code "93") (name "unconnected-(U5-RTS-Pad4)") (class "Default")
      (node (ref "U5") (pin "4") (pinfunction "RTS_4") (pintype "input+no_connect"))
    )
    (net (code "94") (name "unconnected-(U5-USB_D+-Pad20)") (class "Default")
      (node (ref "U5") (pin "20") (pinfunction "USB_D+_20") (pintype "input+no_connect"))
    )
    (net (code "95") (name "unconnected-(U5-USB_D--Pad15)") (class "Default")
      (node (ref "U5") (pin "15") (pinfunction "USB_D-_15") (pintype "input+no_connect"))
    )
    (net (code "96") (name "unconnected-(U8-NC-Pad6)") (class "Default")
      (node (ref "U8") (pin "6") (pinfunction "NC_6") (pintype "input+no_connect"))
    )
    (net (code "97") (name "unconnected-(USB1-EH-Pad6)") (class "Default")
      (node (ref "USB1") (pin "6") (pinfunction "EH_6") (pintype "input+no_connect"))
    )
    (net (code "98") (name "unconnected-(USB1-ID-Pad4)") (class "Default")
      (node (ref "USB1") (pin "4") (pinfunction "ID_4") (pintype "input+no_connect"))
    )
  )
)
